# Sheet1.net
KiCad netlist of a schematic drawn in Altium Designer
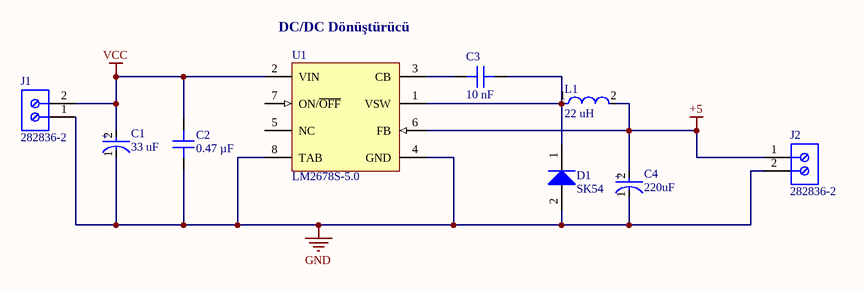
[diagram p0: Sheet1.SchDoc]

(export (version "E")
  (design (tool "Eeschema 10.0.6"))
  (components
    (comp (ref "C1")
      (value "33 uF")
      (footprint "FP-FK-D-MFG")
      (description "CAP ALUM 47UF 20% 35V SMD")
      (fields
        (field (name "MANUFACTURER") "Panasonic")
        (field (name "OCTOPART") "https://octopart.com/eeefk1v470p-panasonic-4642848")
      )
      (libsource (lib "Altium Content Vault") (part "a00bbbee19879c290e62620ae7e47b1"))
    )
    (comp (ref "C2")
      (value "0.47 µF")
      (footprint "CAP 1206_3216 - 0.8MM")
      (description "CAP CER 0.47UF 50V X7R 1206")
      (fields
        (field (name "PART NUMBER") "CL31B474KBHNNNE")
        (field (name "MANUFACTURER") "Samsung Electro-Mechanics")
      )
      (libsource (lib "Celestial Altium Library - altium_library") (part "Capacitor"))
    )
    (comp (ref "C3")
      (value "10 nF")
      (footprint "CAP 0805_2012")
      (description "CAP CER 10000PF 50V X7R 0805")
      (fields
        (field (name "PART NUMBER") "CL21B103KB6WPNC")
        (field (name "MANUFACTURER") "Samsung Electro-Mechanics")
      )
      (libsource (lib "Celestial Altium Library - altium_library") (part "Capacitor"))
    )
    (comp (ref "C4")
      (value "220uF")
      (footprint "FP-UWT1H101MNL1GS-MFG")
      (description "CAP ALUM 100UF 20% 50V SMD")
      (fields (field (name "TOLERANCE") "20%") (field (name "VOLTAGE") "50V"))
      (libsource (lib "Altium Content Vault") (part "203bc49f2ac43e59fd269a8c329ed05"))
    )
    (comp (ref "D1")
      (value "SK54")
      (footprint "ONSC-SOD-323-2-477-02_V")
      (description "Schottky Barrier Diode, 2-Pin SOD-323, Pb-Free, Tape and Reel")
      (fields (field (name "PARTNUMBER") "BAT54HT1G") (field (name "MANUFACTURER") "On Semiconductor"))
      (libsource (lib "Altium Content Vault") (part "ONSC-D-K1A2-2"))
    )
    (comp (ref "J1")
      (value "282836-2")
      (footprint "TECO-282836-2_V")
      (description "Female Header, Pitch 5 mm, 1 x 2 Position, Height 10 mm, Tail Length 3.5 mm, Rohs, Bulk")
      (fields (field (name "VOLTAGE") "300V") (field (name "MANUFACTURER") "TE Connectivity"))
      (libsource (lib "Altium Content Vault") (part "CN-1P-F-TB2"))
    )
    (comp (ref "J2")
      (value "282836-2")
      (footprint "TECO-282836-2_V")
      (description "Female Header, Pitch 5 mm, 1 x 2 Position, Height 10 mm, Tail Length 3.5 mm, Rohs, Bulk")
      (fields (field (name "VOLTAGE") "300V") (field (name "MANUFACTURER") "TE Connectivity"))
      (libsource (lib "Altium Content Vault") (part "CN-1P-F-TB2"))
    )
    (comp (ref "L1")
      (value "22 uH")
      (footprint "FP-SRR1260-MFG")
      (description "FIXED IND 15UH 5A 27 MOHM SMD")
      (fields (field (name "TOLERANCE") "20%"))
      (libsource (lib "Altium Content Vault") (part "725321dda6339637d4d059423bc1c3c"))
    )
    (comp (ref "U1")
      (value "LM2678S-5.0")
      (footprint "KTW0007B_N")
      (description "SIMPLE SWITCHER® High Efficiency 5A Step-Down Voltage Regulator, 7-pin TO-263")
      (fields (field (name "MANUFACTURER") "Texas Instruments"))
      (libsource (lib "Altium Content Vault") (part "PM-REG-LM2678S"))
    )
  )
  (nets
    (net (code "1") (name "+5") (class "Default")
      (node (ref "C4") (pin "2") (pinfunction "A_2") (pintype "passive"))
      (node (ref "J2") (pin "1") (pinfunction "1_1") (pintype "passive"))
      (node (ref "L1") (pin "2") (pinfunction "2_2") (pintype "passive"))
      (node (ref "U1") (pin "6") (pinfunction "FB_6") (pintype "input"))
    )
    (net (code "2") (name "GND") (class "Default")
      (node (ref "C1") (pin "1") (pinfunction "C_1") (pintype "passive"))
      (node (ref "C2") (pin "1") (pinfunction "1_1") (pintype "passive"))
      (node (ref "C4") (pin "1") (pinfunction "C_1") (pintype "passive"))
      (node (ref "D1") (pin "2") (pinfunction "A_2") (pintype "passive"))
      (node (ref "J1") (pin "1") (pinfunction "1_1") (pintype "passive"))
      (node (ref "J2") (pin "2") (pinfunction "2_2") (pintype "passive"))
      (node (ref "U1") (pin "4") (pinfunction "GND_4") (pintype "power_in"))
      (node (ref "U1") (pin "8") (pinfunction "TAB_8") (pintype "power_in"))
    )
    (net (code "3") (name "Net-(D1-K)") (class "Default")
      (node (ref "C3") (pin "2") (pinfunction "2_2") (pintype "passive"))
      (node (ref "D1") (pin "1") (pinfunction "K_1") (pintype "passive"))
      (node (ref "L1") (pin "1") (pinfunction "1_1") (pintype "passive"))
      (node (ref "U1") (pin "1") (pinfunction "VSW_1") (pintype "power_in"))
    )
    (net (code "4") (name "Net-(U1-CB)") (class "Default")
      (node (ref "C3") (pin "1") (pinfunction "1_1") (pintype "passive"))
      (node (ref "U1") (pin "3") (pinfunction "CB_3") (pintype "passive"))
    )
    (net (code "5") (name "VCC") (class "Default")
      (node (ref "C1") (pin "2") (pinfunction "A_2") (pintype "passive"))
      (node (ref "C2") (pin "2") (pinfunction "2_2") (pintype "passive"))
      (node (ref "J1") (pin "2") (pinfunction "2_2") (pintype "passive"))
      (node (ref "U1") (pin "2") (pinfunction "VIN_2") (pintype "power_in"))
    )
    (net (code "6") (name "unconnected-(U1-NC-Pad5)") (class "Default")
      (node (ref "U1") (pin "5") (pinfunction "NC_5") (pintype "passive"))
    )
    (net (code "7") (name "unconnected-(U1-ON{slash}~{OFF}-Pad7)") (class "Default")
      (node (ref "U1") (pin "7") (pinfunction "ON/~{OFF}_7") (pintype "input"))
    )
  )
)
